# 1.net
KiCad netlist of a schematic drawn in Altium Designer
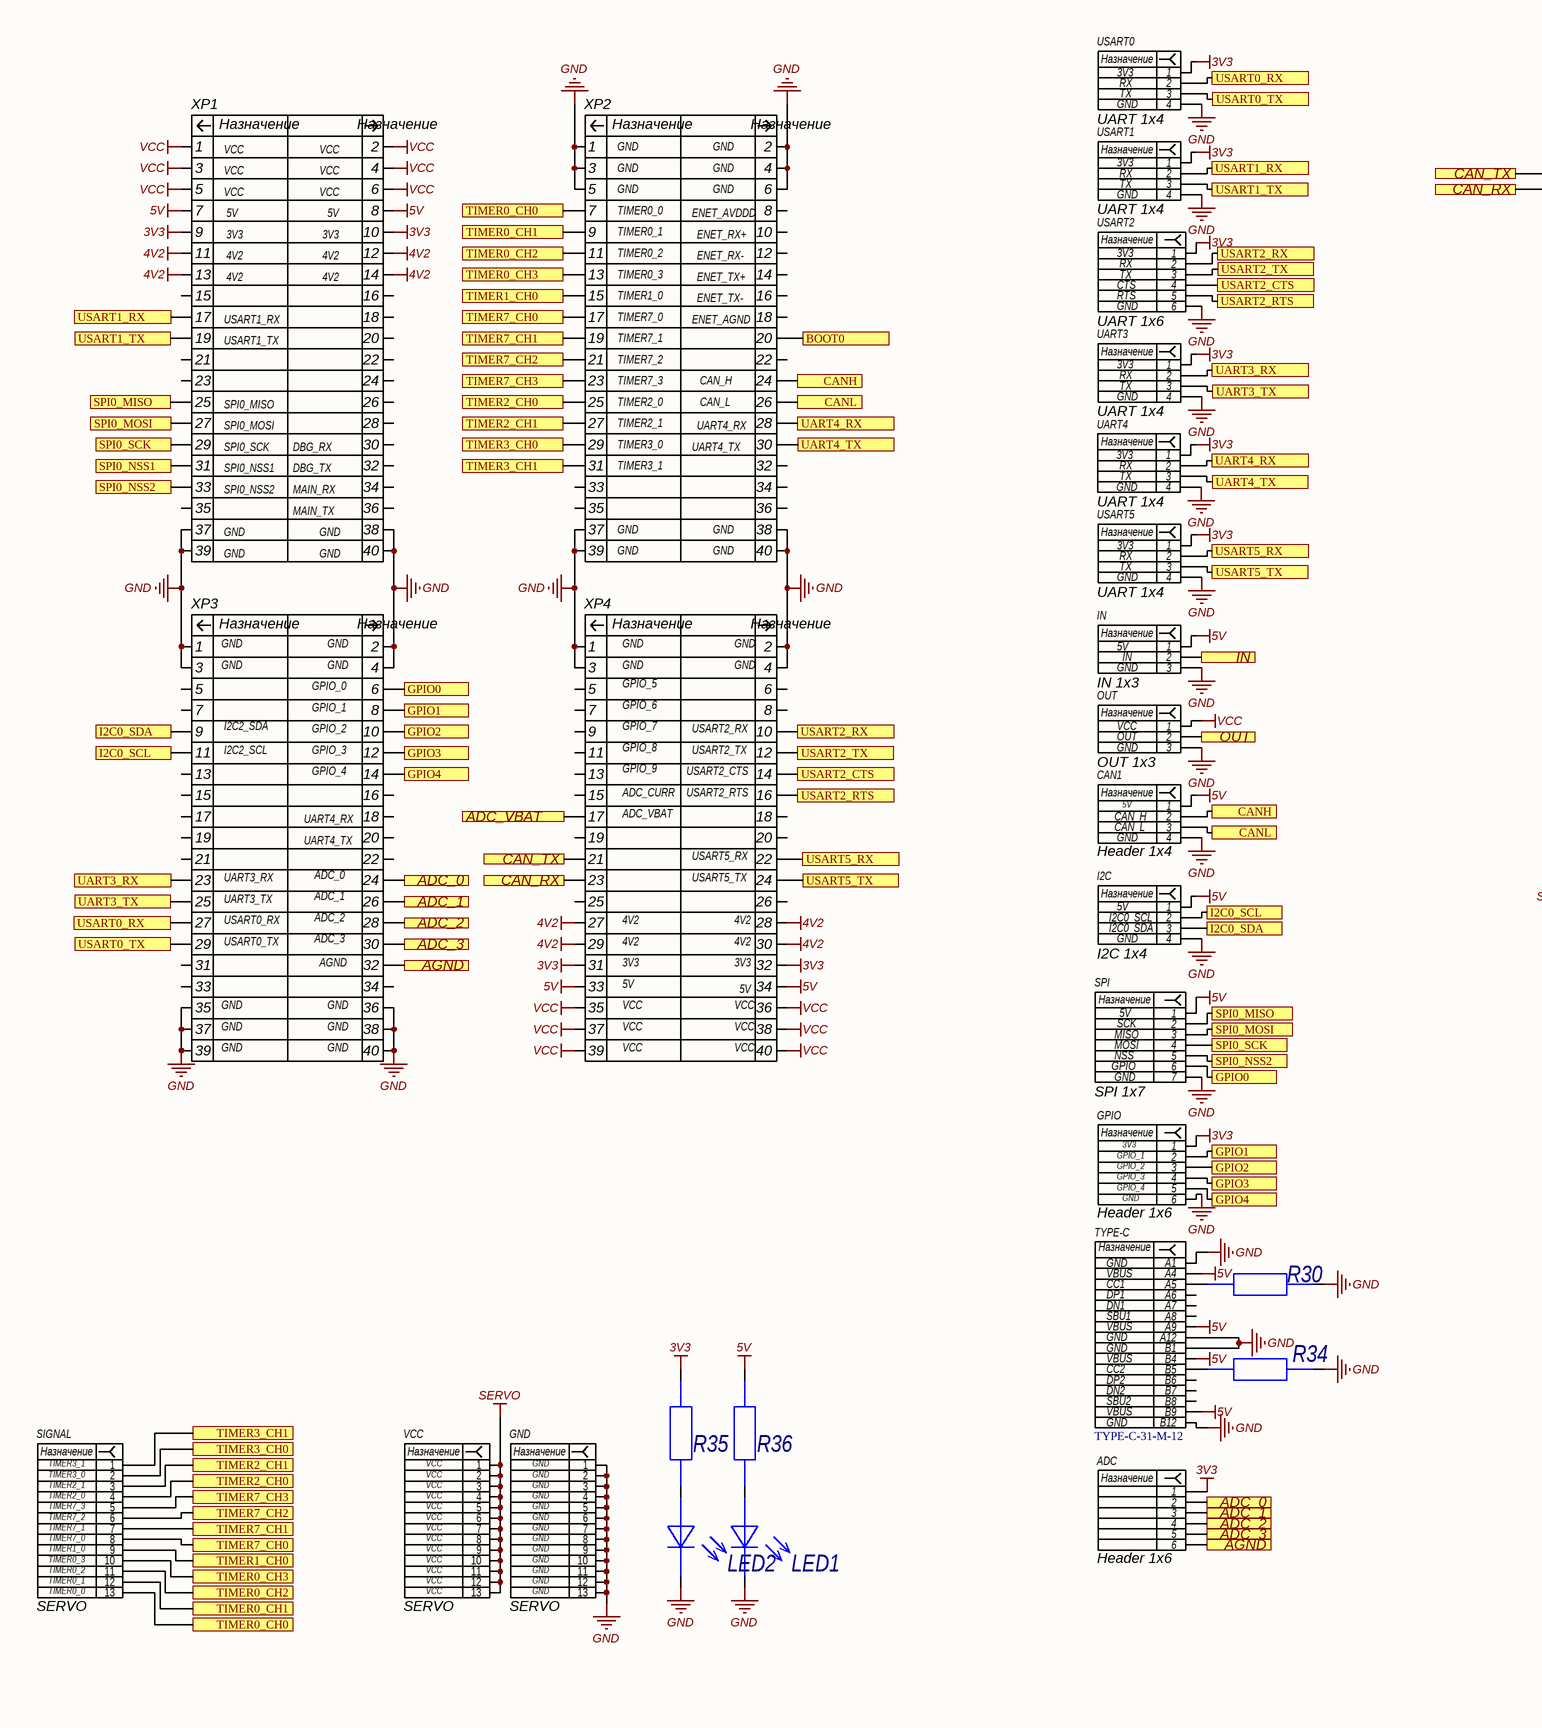
[diagram p0: нижняя плата версия 1.SchDoc, left]
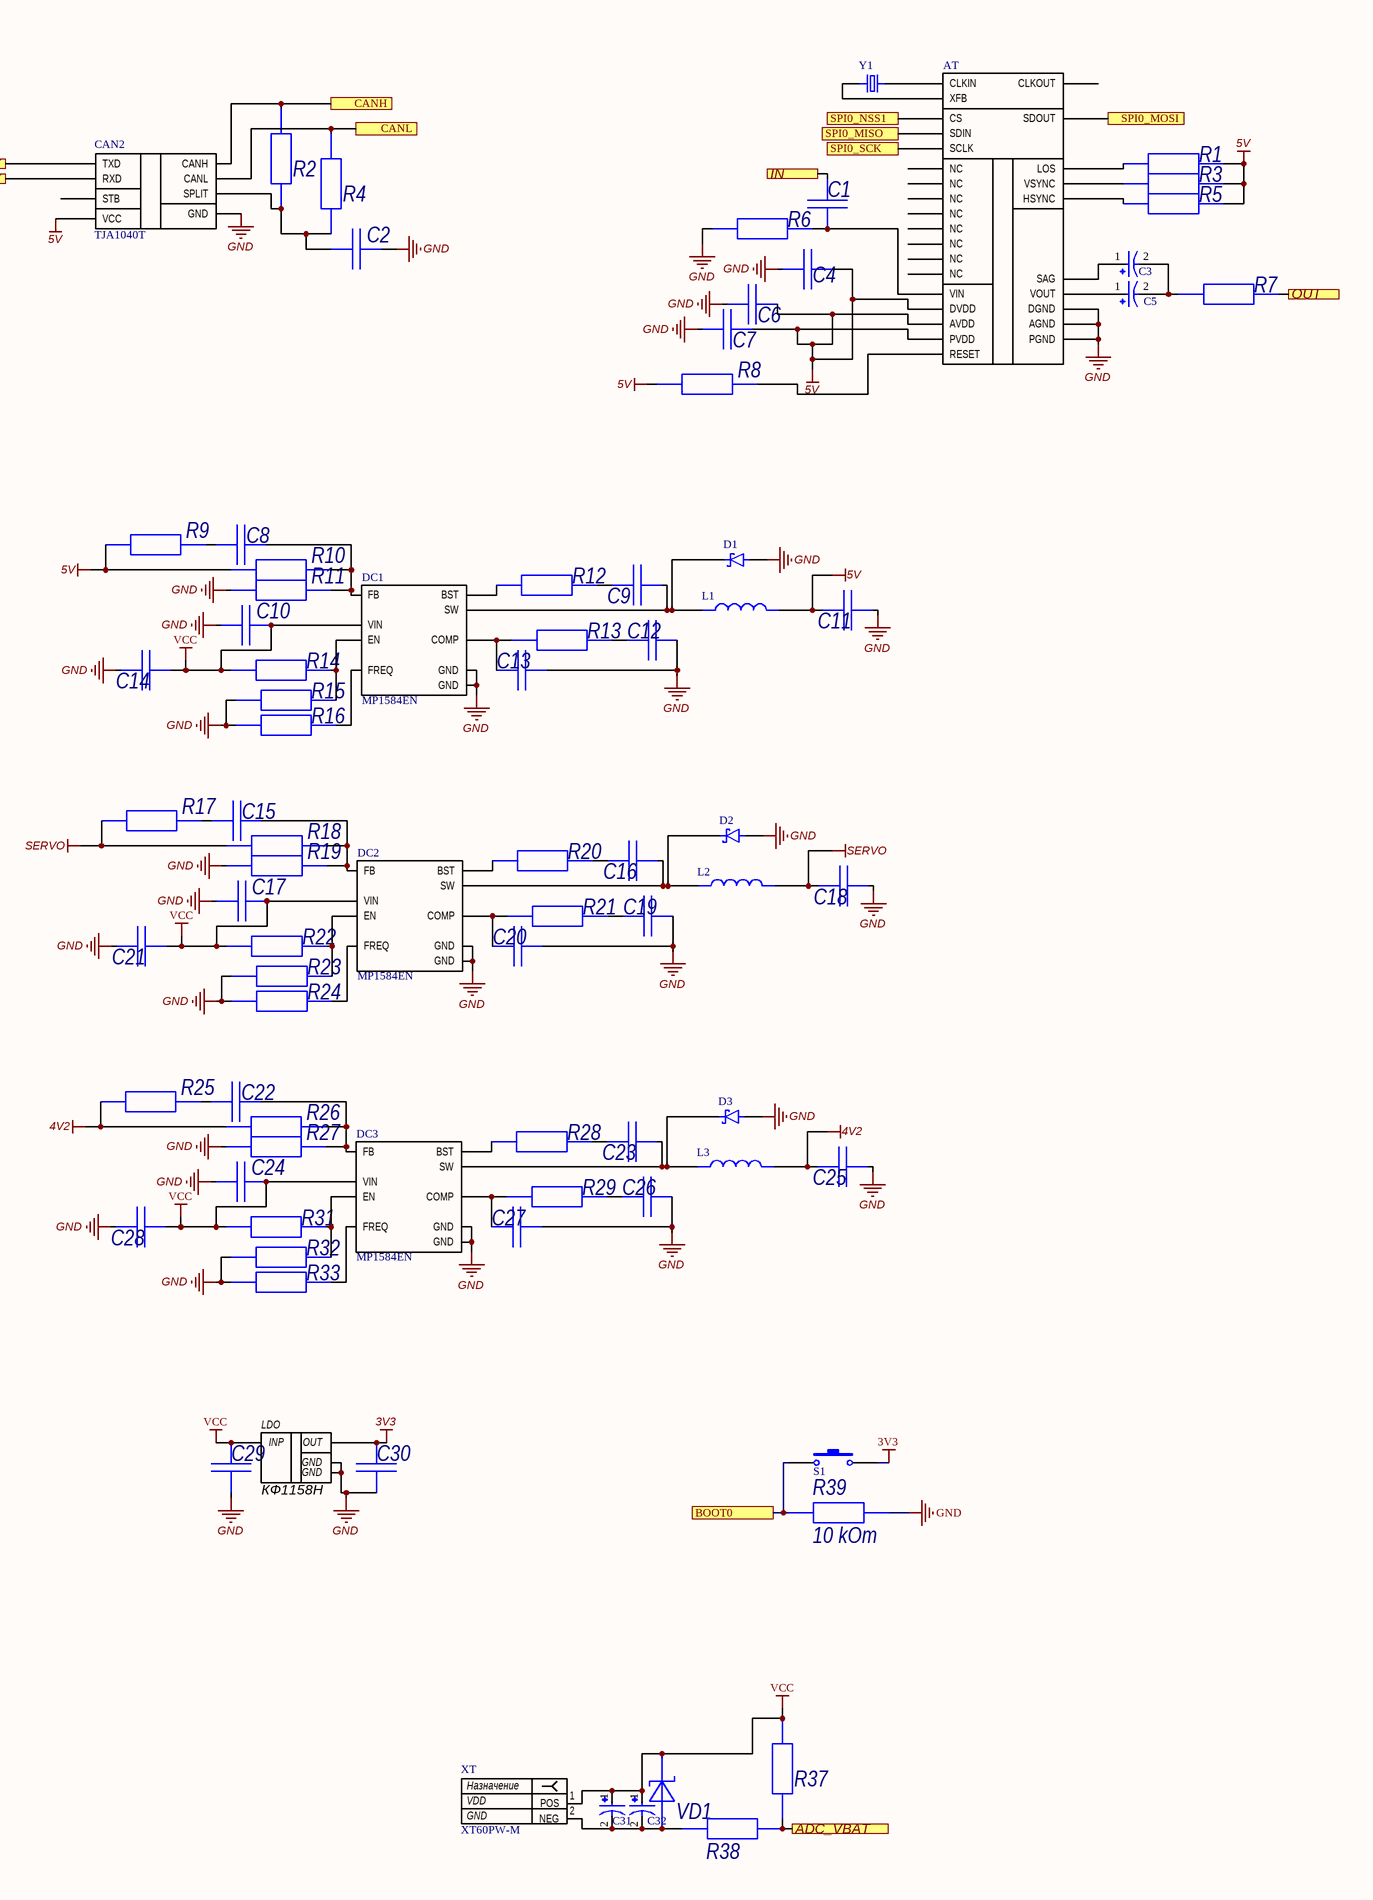
[diagram p1: нижняя плата версия 1.SchDoc, right]

(export (version "E")
  (design (tool "Eeschema 10.0.6"))
  (components
    (comp (ref "ADC")
      (value "Header 1x6")
      (footprint "PicoBlade 6pin")
      (libsource (lib "полётный контроллер") (part "Header 1x6"))
    )
    (comp (ref "AT")
      (value "AT7456")
      (footprint "at7456")
      (description "OSD")
      (libsource (lib "полётный контроллер") (part "AT7456"))
    )
    (comp (ref "C1")
      (value "Capacitor")
      (footprint "C0603")
      (fields (field (name "PUBLISHER") "Andrew Danich"))
      (libsource (lib "Capacitor GOST") (part "Capacitor"))
    )
    (comp (ref "C2")
      (value "4.7 uF")
      (footprint "C0603")
      (fields (field (name "PUBLISHER") "Andrew Danich"))
      (libsource (lib "Capacitor GOST") (part "Capacitor"))
    )
    (comp (ref "C3")
      (value "T493B105K025BC6120")
      (footprint "CAPPM3528X210N")
      (description "Tantalum Surface Mount Capacitors")
      (fields (field (name "MF") "KEMET"))
      (libsource (lib "") (part "T493B105K025BC6120_1"))
    )
    (comp (ref "C4")
      (value "Capacitor")
      (footprint "C0603")
      (fields (field (name "PUBLISHER") "Andrew Danich"))
      (libsource (lib "Capacitor GOST") (part "Capacitor"))
    )
    (comp (ref "C5")
      (value "T493B105K025BC6120")
      (footprint "CAPPM3528X210N")
      (description "Tantalum Surface Mount Capacitors")
      (fields (field (name "MF") "KEMET"))
      (libsource (lib "") (part "T493B105K025BC6120_1"))
    )
    (comp (ref "C6")
      (value "Capacitor")
      (footprint "C0603")
      (fields (field (name "PUBLISHER") "Andrew Danich"))
      (libsource (lib "Capacitor GOST") (part "Capacitor"))
    )
    (comp (ref "C7")
      (value "Capacitor")
      (footprint "C0603")
      (fields (field (name "PUBLISHER") "Andrew Danich"))
      (libsource (lib "Capacitor GOST") (part "Capacitor"))
    )
    (comp (ref "C8")
      (value "22 pF")
      (footprint "C0603")
      (fields (field (name "PUBLISHER") "Andrew Danich"))
      (libsource (lib "Capacitor GOST") (part "Capacitor"))
    )
    (comp (ref "C9")
      (value "0.1 uF")
      (footprint "C0603")
      (fields (field (name "PUBLISHER") "Andrew Danich"))
      (libsource (lib "Capacitor GOST") (part "Capacitor"))
    )
    (comp (ref "C10")
      (value "0.1 uF")
      (footprint "C0603")
      (fields (field (name "PUBLISHER") "Andrew Danich"))
      (libsource (lib "Capacitor GOST") (part "Capacitor"))
    )
    (comp (ref "C11")
      (value "22 uF")
      (footprint "C0603")
      (fields (field (name "PUBLISHER") "Andrew Danich"))
      (libsource (lib "Capacitor GOST") (part "Capacitor"))
    )
    (comp (ref "C12")
      (value "330 pF")
      (footprint "C0603")
      (fields (field (name "PUBLISHER") "Andrew Danich"))
      (libsource (lib "Capacitor GOST") (part "Capacitor"))
    )
    (comp (ref "C13")
      (value "1 pF")
      (footprint "C0603")
      (fields (field (name "PUBLISHER") "Andrew Danich"))
      (libsource (lib "Capacitor GOST") (part "Capacitor"))
    )
    (comp (ref "C14")
      (value "4.7 uF")
      (footprint "C0603")
      (fields (field (name "PUBLISHER") "Andrew Danich"))
      (libsource (lib "Capacitor GOST") (part "Capacitor"))
    )
    (comp (ref "C15")
      (value "22 pF")
      (footprint "C0603")
      (fields (field (name "PUBLISHER") "Andrew Danich"))
      (libsource (lib "Capacitor GOST") (part "Capacitor"))
    )
    (comp (ref "C16")
      (value "0.1 uF")
      (footprint "C0603")
      (fields (field (name "PUBLISHER") "Andrew Danich"))
      (libsource (lib "Capacitor GOST") (part "Capacitor"))
    )
    (comp (ref "C17")
      (value "0.1 uF")
      (footprint "C0603")
      (fields (field (name "PUBLISHER") "Andrew Danich"))
      (libsource (lib "Capacitor GOST") (part "Capacitor"))
    )
    (comp (ref "C18")
      (value "22 uF")
      (footprint "C0603")
      (fields (field (name "PUBLISHER") "Andrew Danich"))
      (libsource (lib "Capacitor GOST") (part "Capacitor"))
    )
    (comp (ref "C19")
      (value "330 pF")
      (footprint "C0603")
      (fields (field (name "PUBLISHER") "Andrew Danich"))
      (libsource (lib "Capacitor GOST") (part "Capacitor"))
    )
    (comp (ref "C20")
      (value "1 pF")
      (footprint "C0603")
      (fields (field (name "PUBLISHER") "Andrew Danich"))
      (libsource (lib "Capacitor GOST") (part "Capacitor"))
    )
    (comp (ref "C21")
      (value "4.7 uF")
      (footprint "C0603")
      (fields (field (name "PUBLISHER") "Andrew Danich"))
      (libsource (lib "Capacitor GOST") (part "Capacitor"))
    )
    (comp (ref "C22")
      (value "22 pF")
      (footprint "C0603")
      (fields (field (name "PUBLISHER") "Andrew Danich"))
      (libsource (lib "Capacitor GOST") (part "Capacitor"))
    )
    (comp (ref "C23")
      (value "0.1 uF")
      (footprint "C0603")
      (fields (field (name "PUBLISHER") "Andrew Danich"))
      (libsource (lib "Capacitor GOST") (part "Capacitor"))
    )
    (comp (ref "C24")
      (value "0.1 uF")
      (footprint "C0603")
      (fields (field (name "PUBLISHER") "Andrew Danich"))
      (libsource (lib "Capacitor GOST") (part "Capacitor"))
    )
    (comp (ref "C25")
      (value "33 uF")
      (footprint "C0603")
      (fields (field (name "PUBLISHER") "Andrew Danich"))
      (libsource (lib "Capacitor GOST") (part "Capacitor"))
    )
    (comp (ref "C26")
      (value "330 pF")
      (footprint "C0603")
      (fields (field (name "PUBLISHER") "Andrew Danich"))
      (libsource (lib "Capacitor GOST") (part "Capacitor"))
    )
    (comp (ref "C27")
      (value "2 pF")
      (footprint "C0603")
      (fields (field (name "PUBLISHER") "Andrew Danich"))
      (libsource (lib "Capacitor GOST") (part "Capacitor"))
    )
    (comp (ref "C28")
      (value "4.7 uF")
      (footprint "C0603")
      (fields (field (name "PUBLISHER") "Andrew Danich"))
      (libsource (lib "Capacitor GOST") (part "Capacitor"))
    )
    (comp (ref "C29")
      (value "0.1 uF")
      (footprint "C0603")
      (fields (field (name "PUBLISHER") "Andrew Danich"))
      (libsource (lib "Capacitor GOST") (part "Capacitor"))
    )
    (comp (ref "C30")
      (value "10 uF")
      (footprint "C0603")
      (fields (field (name "PUBLISHER") "Andrew Danich"))
      (libsource (lib "Capacitor GOST") (part "Capacitor"))
    )
    (comp (ref "C31")
      (value "T493B105K025BC6120")
      (footprint "CAPPM3528X210N")
      (description "Tantalum Surface Mount Capacitors")
      (fields (field (name "MF") "KEMET"))
      (libsource (lib "T493B105K025BC6120") (part "T493B105K025BC6120"))
    )
    (comp (ref "C32")
      (value "T493B105K025BC6120")
      (footprint "CAPPM3528X210N")
      (description "Tantalum Surface Mount Capacitors")
      (fields (field (name "MF") "KEMET"))
      (libsource (lib "T493B105K025BC6120") (part "T493B105K025BC6120"))
    )
    (comp (ref "CAN1")
      (value "Header 1x4")
      (footprint "PicoBlade 4pin")
      (libsource (lib "полётный контроллер") (part "Header 1x4"))
    )
    (comp (ref "CAN2")
      (value "TJA1040T")
      (footprint "SO-8_S")
      (libsource (lib "полётный контроллер") (part "TJA1040T"))
    )
    (comp (ref "D1")
      (value "B340A-13-F")
      (footprint "DIOM5226X240N")
      (description "Diode, Rectifier, 3a, 40v, Do-214ac, Full Reel")
      (libsource (lib "B340A-13-F") (part "B340A-13-F"))
    )
    (comp (ref "D2")
      (value "B340A-13-F")
      (footprint "DIOM5226X240N")
      (description "Diode, Rectifier, 3a, 40v, Do-214ac, Full Reel")
      (libsource (lib "B340A-13-F") (part "B340A-13-F"))
    )
    (comp (ref "D3")
      (value "B340A-13-F")
      (footprint "DIOM5226X240N")
      (description "Diode, Rectifier, 3a, 40v, Do-214ac, Full Reel")
      (libsource (lib "B340A-13-F") (part "B340A-13-F"))
    )
    (comp (ref "DC1")
      (value "MP1584EN")
      (footprint "SOIC127P600X170-9N")
      (libsource (lib "полётный контроллер") (part "MP1584EN"))
    )
    (comp (ref "DC2")
      (value "MP1584EN")
      (footprint "SOIC127P600X170-9N")
      (libsource (lib "полётный контроллер") (part "MP1584EN"))
    )
    (comp (ref "DC3")
      (value "MP1584EN")
      (footprint "SOIC127P600X170-9N")
      (libsource (lib "полётный контроллер") (part "MP1584EN"))
    )
    (comp (ref "GND")
      (value "SERVO")
      (footprint "SERV")
      (libsource (lib "полётный контроллер") (part "SERVO"))
    )
    (comp (ref "GPIO")
      (value "Header 1x6")
      (footprint "PicoBlade 6pin")
      (libsource (lib "полётный контроллер") (part "Header 1x6"))
    )
    (comp (ref "I2C")
      (value "I2C 1x4")
      (footprint "PicoBlade 4pin")
      (libsource (lib "полётный контроллер") (part "I2C 1x4"))
    )
    (comp (ref "IN")
      (value "IN 1x3")
      (footprint "PicoBlade 3pin")
      (libsource (lib "полётный контроллер") (part "IN 1x3"))
    )
    (comp (ref "L1")
      (value "12.3 uH")
      (footprint "IND_VLS6045EX-150M")
      (description "15 ÂµH Shielded Drum Core, Wirewound Inductor 2.5 A 75mOhm Nonstandard")
      (fields (field (name "MF") "TDK") (field (name "MP") "VLS6045EX-150M"))
      (libsource (lib "VLS6045EX-150M") (part "VLS6045EX-150M"))
    )
    (comp (ref "L2")
      (value "12.3 uH")
      (footprint "IND_VLS6045EX-150M")
      (description "15 ÂµH Shielded Drum Core, Wirewound Inductor 2.5 A 75mOhm Nonstandard")
      (fields (field (name "MF") "TDK") (field (name "MP") "VLS6045EX-150M"))
      (libsource (lib "VLS6045EX-150M") (part "VLS6045EX-150M"))
    )
    (comp (ref "L3")
      (value "12.3 uH")
      (footprint "IND_VLS6045EX-150M")
      (description "15 ÂµH Shielded Drum Core, Wirewound Inductor 2.5 A 75mOhm Nonstandard")
      (fields (field (name "MF") "TDK") (field (name "MP") "VLS6045EX-150M"))
      (libsource (lib "VLS6045EX-150M") (part "VLS6045EX-150M"))
    )
    (comp (ref "LDO")
      (value "КФ1158Н")
      (footprint "ТО-263")
      (libsource (lib "полётный контроллер") (part "КФ1158Н"))
    )
    (comp (ref "LED1")
      (value "Text")
      (footprint "LD0805")
      (fields (field (name "PUBLISHER") "Andrew Danich"))
      (libsource (lib "Led GOST") (part "Led-1"))
    )
    (comp (ref "LED2")
      (value "Text")
      (footprint "LD0805")
      (fields (field (name "PUBLISHER") "Andrew Danich"))
      (libsource (lib "Led GOST") (part "Led-1"))
    )
    (comp (ref "OUT")
      (value "OUT 1x3")
      (footprint "PicoBlade 3pin")
      (libsource (lib "полётный контроллер") (part "OUT 1x3"))
    )
    (comp (ref "R1")
      (value "1 kOm")
      (footprint "R0603")
      (fields (field (name "PUBLISHER") "Andrew Danich"))
      (libsource (lib "Resistor GOST") (part "Resistor"))
    )
    (comp (ref "R2")
      (value "~")
      (footprint "R0603")
      (fields (field (name "PUBLISHER") "Andrew Danich"))
      (libsource (lib "Resistor GOST") (part "Resistor"))
    )
    (comp (ref "R3")
      (value "1 kOm")
      (footprint "R0603")
      (fields (field (name "PUBLISHER") "Andrew Danich"))
      (libsource (lib "Resistor GOST") (part "Resistor"))
    )
    (comp (ref "R4")
      (value "~")
      (footprint "R0603")
      (fields (field (name "PUBLISHER") "Andrew Danich"))
      (libsource (lib "Resistor GOST") (part "Resistor"))
    )
    (comp (ref "R5")
      (value "1 kOm")
      (footprint "R0603")
      (fields (field (name "PUBLISHER") "Andrew Danich"))
      (libsource (lib "Resistor GOST") (part "Resistor"))
    )
    (comp (ref "R6")
      (value "10 kOm")
      (footprint "R0603")
      (fields (field (name "PUBLISHER") "Andrew Danich"))
      (libsource (lib "Resistor GOST") (part "Resistor"))
    )
    (comp (ref "R7")
      (value "10 kOm")
      (footprint "R0603")
      (fields (field (name "PUBLISHER") "Andrew Danich"))
      (libsource (lib "Resistor GOST") (part "Resistor"))
    )
    (comp (ref "R8")
      (value "10 kOm")
      (footprint "R0603")
      (fields (field (name "PUBLISHER") "Andrew Danich"))
      (libsource (lib "Resistor GOST") (part "Resistor"))
    )
    (comp (ref "R9")
      (value "0")
      (footprint "R0603")
      (fields (field (name "PUBLISHER") "Andrew Danich"))
      (libsource (lib "Resistor GOST") (part "Resistor"))
    )
    (comp (ref "R10")
      (value "124 kOm")
      (footprint "R0603")
      (fields (field (name "PUBLISHER") "Andrew Danich"))
      (libsource (lib "Resistor GOST") (part "Resistor"))
    )
    (comp (ref "R11")
      (value "23.7 kOm")
      (footprint "R0603")
      (fields (field (name "PUBLISHER") "Andrew Danich"))
      (libsource (lib "Resistor GOST") (part "Resistor"))
    )
    (comp (ref "R12")
      (value "0")
      (footprint "R0603")
      (fields (field (name "PUBLISHER") "Andrew Danich"))
      (libsource (lib "Resistor GOST") (part "Resistor"))
    )
    (comp (ref "R13")
      (value "76.8 kOm")
      (footprint "R0603")
      (fields (field (name "PUBLISHER") "Andrew Danich"))
      (libsource (lib "Resistor GOST") (part "Resistor"))
    )
    (comp (ref "R14")
      (value "100 kOm")
      (footprint "R0603")
      (fields (field (name "PUBLISHER") "Andrew Danich"))
      (libsource (lib "Resistor GOST") (part "Resistor"))
    )
    (comp (ref "R15")
      (value "18.7 kOm")
      (footprint "R0603")
      (fields (field (name "PUBLISHER") "Andrew Danich"))
      (libsource (lib "Resistor GOST") (part "Resistor"))
    )
    (comp (ref "R16")
      (value "193.38 kOm")
      (footprint "R0603")
      (fields (field (name "PUBLISHER") "Andrew Danich"))
      (libsource (lib "Resistor GOST") (part "Resistor"))
    )
    (comp (ref "R17")
      (value "0")
      (footprint "R0603")
      (fields (field (name "PUBLISHER") "Andrew Danich"))
      (libsource (lib "Resistor GOST") (part "Resistor"))
    )
    (comp (ref "R18")
      (value "124 kOm")
      (footprint "R0603")
      (fields (field (name "PUBLISHER") "Andrew Danich"))
      (libsource (lib "Resistor GOST") (part "Resistor"))
    )
    (comp (ref "R19")
      (value "23.7 kOm")
      (footprint "R0603")
      (fields (field (name "PUBLISHER") "Andrew Danich"))
      (libsource (lib "Resistor GOST") (part "Resistor"))
    )
    (comp (ref "R20")
      (value "0")
      (footprint "R0603")
      (fields (field (name "PUBLISHER") "Andrew Danich"))
      (libsource (lib "Resistor GOST") (part "Resistor"))
    )
    (comp (ref "R21")
      (value "76.8 kOm")
      (footprint "R0603")
      (fields (field (name "PUBLISHER") "Andrew Danich"))
      (libsource (lib "Resistor GOST") (part "Resistor"))
    )
    (comp (ref "R22")
      (value "100 kOm")
      (footprint "R0603")
      (fields (field (name "PUBLISHER") "Andrew Danich"))
      (libsource (lib "Resistor GOST") (part "Resistor"))
    )
    (comp (ref "R23")
      (value "18.7 kOm")
      (footprint "R0603")
      (fields (field (name "PUBLISHER") "Andrew Danich"))
      (libsource (lib "Resistor GOST") (part "Resistor"))
    )
    (comp (ref "R24")
      (value "193.38 kOm")
      (footprint "R0603")
      (fields (field (name "PUBLISHER") "Andrew Danich"))
      (libsource (lib "Resistor GOST") (part "Resistor"))
    )
    (comp (ref "R25")
      (value "0")
      (footprint "R0603")
      (fields (field (name "PUBLISHER") "Andrew Danich"))
      (libsource (lib "Resistor GOST") (part "Resistor"))
    )
    (comp (ref "R26")
      (value "124 kOm")
      (footprint "R0603")
      (fields (field (name "PUBLISHER") "Andrew Danich"))
      (libsource (lib "Resistor GOST") (part "Resistor"))
    )
    (comp (ref "R27")
      (value "29 kOm")
      (footprint "R0603")
      (fields (field (name "PUBLISHER") "Andrew Danich"))
      (libsource (lib "Resistor GOST") (part "Resistor"))
    )
    (comp (ref "R28")
      (value "0")
      (footprint "R0603")
      (fields (field (name "PUBLISHER") "Andrew Danich"))
      (libsource (lib "Resistor GOST") (part "Resistor"))
    )
    (comp (ref "R29")
      (value "100 kOm")
      (footprint "R0603")
      (fields (field (name "PUBLISHER") "Andrew Danich"))
      (libsource (lib "Resistor GOST") (part "Resistor"))
    )
    (comp (ref "R30")
      (value "10 kOm")
      (footprint "R0603")
      (fields (field (name "PUBLISHER") "Andrew Danich"))
      (libsource (lib "Resistor GOST") (part "Resistor"))
    )
    (comp (ref "R31")
      (value "100 kOm")
      (footprint "R0603")
      (fields (field (name "PUBLISHER") "Andrew Danich"))
      (libsource (lib "Resistor GOST") (part "Resistor"))
    )
    (comp (ref "R32")
      (value "18.7 kOm")
      (footprint "R0603")
      (fields (field (name "PUBLISHER") "Andrew Danich"))
      (libsource (lib "Resistor GOST") (part "Resistor"))
    )
    (comp (ref "R33")
      (value "193.38 kOm")
      (footprint "R0603")
      (fields (field (name "PUBLISHER") "Andrew Danich"))
      (libsource (lib "Resistor GOST") (part "Resistor"))
    )
    (comp (ref "R34")
      (value "10 kOm")
      (footprint "R0603")
      (fields (field (name "PUBLISHER") "Andrew Danich"))
      (libsource (lib "Resistor GOST") (part "Resistor"))
    )
    (comp (ref "R35")
      (value "10 kOm")
      (footprint "R0603")
      (fields (field (name "PUBLISHER") "Andrew Danich"))
      (libsource (lib "Resistor GOST") (part "Resistor"))
    )
    (comp (ref "R36")
      (value "10 kOm")
      (footprint "R0603")
      (fields (field (name "PUBLISHER") "Andrew Danich"))
      (libsource (lib "Resistor GOST") (part "Resistor"))
    )
    (comp (ref "R37")
      (value "~")
      (footprint "R0603")
      (fields (field (name "PUBLISHER") "Andrew Danich"))
      (libsource (lib "Resistor GOST") (part "Resistor"))
    )
    (comp (ref "R38")
      (value "~")
      (footprint "R0603")
      (fields (field (name "PUBLISHER") "Andrew Danich"))
      (libsource (lib "Resistor GOST") (part "Resistor"))
    )
    (comp (ref "R39")
      (value "10 kOm")
      (footprint "R0603")
      (fields (field (name "PUBLISHER") "Andrew Danich"))
      (libsource (lib "Resistor GOST") (part "Resistor"))
    )
    (comp (ref "S1")
      (value "SW-PB")
      (footprint "SWIT")
      (description "Switch")
      (fields (field (name "PUBLISHER") "Altium Limited"))
      (libsource (lib "Miscellaneous Devices") (part "SW-PB"))
    )
    (comp (ref "SIGNAL")
      (value "SERVO")
      (footprint "SERV")
      (libsource (lib "полётный контроллер") (part "SERVO"))
    )
    (comp (ref "SPI")
      (value "SPI 1x7")
      (footprint "PicoBlade 7pin")
      (libsource (lib "полётный контроллер") (part "SPI 1x7"))
    )
    (comp (ref "TYPE-C")
      (value "TYPE-C-31-M-12")
      (footprint "HRO_TYPE-C-31-M-12")
      (libsource (lib "полётный контроллер") (part "TYPE-C-31-M-12"))
    )
    (comp (ref "UART3")
      (value "UART 1x4")
      (footprint "PicoBlade 4pin")
      (libsource (lib "полётный контроллер") (part "UART 1x4"))
    )
    (comp (ref "UART4")
      (value "UART 1x4")
      (footprint "PicoBlade 4pin")
      (libsource (lib "полётный контроллер") (part "UART 1x4"))
    )
    (comp (ref "USART0")
      (value "UART 1x4")
      (footprint "PicoBlade 4pin")
      (libsource (lib "полётный контроллер") (part "UART 1x4"))
    )
    (comp (ref "USART1")
      (value "UART 1x4")
      (footprint "PicoBlade 4pin")
      (libsource (lib "полётный контроллер") (part "UART 1x4"))
    )
    (comp (ref "USART2")
      (value "UART 1x6")
      (footprint "PicoBlade 6pin")
      (libsource (lib "полётный контроллер") (part "UART 1x6"))
    )
    (comp (ref "USART5")
      (value "UART 1x4")
      (footprint "PicoBlade 4pin")
      (libsource (lib "полётный контроллер") (part "UART 1x4"))
    )
    (comp (ref "VCC")
      (value "SERVO")
      (footprint "SERV")
      (libsource (lib "полётный контроллер") (part "SERVO"))
    )
    (comp (ref "VD1")
      (value "Schottky")
      (footprint "DO-214AA")
      (fields (field (name "PUBLISHER") "Andrew Danich"))
      (libsource (lib "Diode GOST") (part "Schottky"))
    )
    (comp (ref "XP1")
      (value "PLLD-1.27-40S")
      (footprint "Headr 2x20 male")
      (libsource (lib "Разьемы_PLLD_PBD") (part "PLLD-1.27-40S"))
    )
    (comp (ref "XP2")
      (value "PLLD-1.27-40S")
      (footprint "Headr 2x20 male")
      (libsource (lib "Разьемы_PLLD_PBD") (part "PLLD-1.27-40S"))
    )
    (comp (ref "XP3")
      (value "PLLD-1.27-40S")
      (footprint "Headr 2x20 male")
      (libsource (lib "Разьемы_PLLD_PBD") (part "PLLD-1.27-40S"))
    )
    (comp (ref "XP4")
      (value "PLLD-1.27-40S")
      (footprint "Headr 2x20 male")
      (libsource (lib "Разьемы_PLLD_PBD") (part "PLLD-1.27-40S"))
    )
    (comp (ref "XT")
      (value "XT60PW-M")
      (footprint "AMASS_XT60PW-M")
      (libsource (lib "полётный контроллер") (part "XT60PW-M"))
    )
    (comp (ref "Y1")
      (value "ABM7-8.000MHZ-8-R80-D2Y-T")
      (footprint "XTAL_ABM7-8.000MHZ-8-R80-D2Y-T")
      (description "Crystal 22.1184MHz Ã‚Â±20ppm (Tol) Ã‚Â±30ppm (Stability) 18pF FUND 50Ohm 2-Pin Mini-CSMD T/R")
      (libsource (lib "ABM7-8.000MHZ-8-R80-D2Y-T") (part "ABM7-8.000MHZ-8-R80-D2Y-T"))
    )
  )
  (nets
    (net (code "1") (name "/ADC_0") (class "Default")
      (node (ref "ADC") (pin "2") (pinfunction "2_2") (pintype "passive"))
      (node (ref "XP3") (pin "24") (pinfunction "24_24") (pintype "passive"))
    )
    (net (code "2") (name "/ADC_1") (class "Default")
      (node (ref "ADC") (pin "3") (pinfunction "3_3") (pintype "passive"))
      (node (ref "XP3") (pin "26") (pinfunction "26_26") (pintype "passive"))
    )
    (net (code "3") (name "/ADC_2") (class "Default")
      (node (ref "ADC") (pin "4") (pinfunction "4_4") (pintype "passive"))
      (node (ref "XP3") (pin "28") (pinfunction "28_28") (pintype "passive"))
    )
    (net (code "4") (name "/ADC_3") (class "Default")
      (node (ref "ADC") (pin "5") (pinfunction "5_5") (pintype "passive"))
      (node (ref "XP3") (pin "30") (pinfunction "30_30") (pintype "passive"))
    )
    (net (code "5") (name "/ADC_VBAT") (class "Default")
      (node (ref "R37") (pin "2") (pinfunction "2_2") (pintype "passive"))
      (node (ref "R38") (pin "2") (pinfunction "2_2") (pintype "passive"))
      (node (ref "XP4") (pin "17") (pinfunction "17_17") (pintype "passive"))
    )
    (net (code "6") (name "/AGND") (class "Default")
      (node (ref "ADC") (pin "6") (pinfunction "6_6") (pintype "passive"))
      (node (ref "XP3") (pin "32") (pinfunction "32_32") (pintype "passive"))
    )
    (net (code "7") (name "/BOOT0") (class "Default")
      (node (ref "R39") (pin "2") (pinfunction "2_2") (pintype "passive"))
      (node (ref "S1") (pin "1") (pinfunction "1_1") (pintype "passive"))
      (node (ref "XP2") (pin "20") (pinfunction "20_20") (pintype "passive"))
    )
    (net (code "8") (name "/CANH") (class "Default")
      (node (ref "CAN1") (pin "2") (pinfunction "2_2") (pintype "passive"))
      (node (ref "CAN2") (pin "7") (pinfunction "CANH_7") (pintype "passive"))
      (node (ref "R2") (pin "1") (pinfunction "1_1") (pintype "passive"))
      (node (ref "XP2") (pin "24") (pinfunction "24_24") (pintype "passive"))
    )
    (net (code "9") (name "/CANL") (class "Default")
      (node (ref "CAN1") (pin "3") (pinfunction "3_3") (pintype "passive"))
      (node (ref "CAN2") (pin "6") (pinfunction "CANL_6") (pintype "passive"))
      (node (ref "R4") (pin "1") (pinfunction "1_1") (pintype "passive"))
      (node (ref "XP2") (pin "26") (pinfunction "26_26") (pintype "passive"))
    )
    (net (code "10") (name "/CAN_RX") (class "Default")
      (node (ref "CAN2") (pin "4") (pinfunction "RXD_4") (pintype "passive"))
      (node (ref "XP4") (pin "23") (pinfunction "23_23") (pintype "passive"))
    )
    (net (code "11") (name "/CAN_TX") (class "Default")
      (node (ref "CAN2") (pin "1") (pinfunction "TXD_1") (pintype "passive"))
      (node (ref "XP4") (pin "21") (pinfunction "21_21") (pintype "passive"))
    )
    (net (code "12") (name "/GPIO0") (class "Default")
      (node (ref "SPI") (pin "6") (pinfunction "6_6") (pintype "passive"))
      (node (ref "XP3") (pin "6") (pinfunction "6_6") (pintype "passive"))
    )
    (net (code "13") (name "/GPIO1") (class "Default")
      (node (ref "GPIO") (pin "2") (pinfunction "2_2") (pintype "passive"))
      (node (ref "XP3") (pin "8") (pinfunction "8_8") (pintype "passive"))
    )
    (net (code "14") (name "/GPIO2") (class "Default")
      (node (ref "GPIO") (pin "3") (pinfunction "3_3") (pintype "passive"))
      (node (ref "XP3") (pin "10") (pinfunction "10_10") (pintype "passive"))
    )
    (net (code "15") (name "/GPIO3") (class "Default")
      (node (ref "GPIO") (pin "4") (pinfunction "4_4") (pintype "passive"))
      (node (ref "XP3") (pin "12") (pinfunction "12_12") (pintype "passive"))
    )
    (net (code "16") (name "/GPIO4") (class "Default")
      (node (ref "GPIO") (pin "5") (pinfunction "5_5") (pintype "passive"))
      (node (ref "XP3") (pin "14") (pinfunction "14_14") (pintype "passive"))
    )
    (net (code "17") (name "/I2C0_SCL") (class "Default")
      (node (ref "I2C") (pin "2") (pinfunction "2_2") (pintype "passive"))
      (node (ref "XP3") (pin "11") (pinfunction "11_11") (pintype "passive"))
    )
    (net (code "18") (name "/I2C0_SDA") (class "Default")
      (node (ref "I2C") (pin "3") (pinfunction "3_3") (pintype "passive"))
      (node (ref "XP3") (pin "9") (pinfunction "9_9") (pintype "passive"))
    )
    (net (code "19") (name "/IN") (class "Default")
      (node (ref "C1") (pin "2") (pinfunction "2_2") (pintype "passive"))
      (node (ref "IN") (pin "2") (pinfunction "2_2") (pintype "passive"))
    )
    (net (code "20") (name "/OUT") (class "Default")
      (node (ref "OUT") (pin "2") (pinfunction "2_2") (pintype "passive"))
      (node (ref "R7") (pin "2") (pinfunction "2_2") (pintype "passive"))
    )
    (net (code "21") (name "/SPI0_MISO") (class "Default")
      (node (ref "AT") (pin "9") (pinfunction "SDIN_9") (pintype "passive"))
      (node (ref "SPI") (pin "2") (pinfunction "2_2") (pintype "passive"))
      (node (ref "XP1") (pin "25") (pinfunction "25_25") (pintype "passive"))
    )
    (net (code "22") (name "/SPI0_MOSI") (class "Default")
      (node (ref "AT") (pin "11") (pinfunction "SDOUT_11") (pintype "passive"))
      (node (ref "SPI") (pin "3") (pinfunction "3_3") (pintype "passive"))
      (node (ref "XP1") (pin "27") (pinfunction "27_27") (pintype "passive"))
    )
    (net (code "23") (name "/SPI0_NSS1") (class "Default")
      (node (ref "AT") (pin "8") (pinfunction "CS_8") (pintype "passive"))
      (node (ref "XP1") (pin "31") (pinfunction "31_31") (pintype "passive"))
    )
    (net (code "24") (name "/SPI0_NSS2") (class "Default")
      (node (ref "SPI") (pin "5") (pinfunction "5_5") (pintype "passive"))
      (node (ref "XP1") (pin "33") (pinfunction "33_33") (pintype "passive"))
    )
    (net (code "25") (name "/SPI0_SCK") (class "Default")
      (node (ref "AT") (pin "10") (pinfunction "SCLK_10") (pintype "passive"))
      (node (ref "SPI") (pin "4") (pinfunction "4_4") (pintype "passive"))
      (node (ref "XP1") (pin "29") (pinfunction "29_29") (pintype "passive"))
    )
    (net (code "26") (name "/TIMER0_CH0") (class "Default")
      (node (ref "SIGNAL") (pin "13") (pinfunction "13_13") (pintype "passive"))
      (node (ref "XP2") (pin "7") (pinfunction "7_7") (pintype "passive"))
    )
    (net (code "27") (name "/TIMER0_CH1") (class "Default")
      (node (ref "SIGNAL") (pin "12") (pinfunction "12_12") (pintype "passive"))
      (node (ref "XP2") (pin "9") (pinfunction "9_9") (pintype "passive"))
    )
    (net (code "28") (name "/TIMER0_CH2") (class "Default")
      (node (ref "SIGNAL") (pin "11") (pinfunction "11_11") (pintype "passive"))
      (node (ref "XP2") (pin "11") (pinfunction "11_11") (pintype "passive"))
    )
    (net (code "29") (name "/TIMER0_CH3") (class "Default")
      (node (ref "SIGNAL") (pin "10") (pinfunction "10_10") (pintype "passive"))
      (node (ref "XP2") (pin "13") (pinfunction "13_13") (pintype "passive"))
    )
    (net (code "30") (name "/TIMER1_CH0") (class "Default")
      (node (ref "SIGNAL") (pin "9") (pinfunction "9_9") (pintype "passive"))
      (node (ref "XP2") (pin "15") (pinfunction "15_15") (pintype "passive"))
    )
    (net (code "31") (name "/TIMER2_CH0") (class "Default")
      (node (ref "SIGNAL") (pin "4") (pinfunction "4_4") (pintype "passive"))
      (node (ref "XP2") (pin "25") (pinfunction "25_25") (pintype "passive"))
    )
    (net (code "32") (name "/TIMER2_CH1") (class "Default")
      (node (ref "SIGNAL") (pin "3") (pinfunction "3_3") (pintype "passive"))
      (node (ref "XP2") (pin "27") (pinfunction "27_27") (pintype "passive"))
    )
    (net (code "33") (name "/TIMER3_CH0") (class "Default")
      (node (ref "SIGNAL") (pin "2") (pinfunction "2_2") (pintype "passive"))
      (node (ref "XP2") (pin "29") (pinfunction "29_29") (pintype "passive"))
    )
    (net (code "34") (name "/TIMER3_CH1") (class "Default")
      (node (ref "SIGNAL") (pin "1") (pinfunction "1_1") (pintype "passive"))
      (node (ref "XP2") (pin "31") (pinfunction "31_31") (pintype "passive"))
    )
    (net (code "35") (name "/TIMER7_CH0") (class "Default")
      (node (ref "SIGNAL") (pin "8") (pinfunction "8_8") (pintype "passive"))
      (node (ref "XP2") (pin "17") (pinfunction "17_17") (pintype "passive"))
    )
    (net (code "36") (name "/TIMER7_CH1") (class "Default")
      (node (ref "SIGNAL") (pin "7") (pinfunction "7_7") (pintype "passive"))
      (node (ref "XP2") (pin "19") (pinfunction "19_19") (pintype "passive"))
    )
    (net (code "37") (name "/TIMER7_CH2") (class "Default")
      (node (ref "SIGNAL") (pin "6") (pinfunction "6_6") (pintype "passive"))
      (node (ref "XP2") (pin "21") (pinfunction "21_21") (pintype "passive"))
    )
    (net (code "38") (name "/TIMER7_CH3") (class "Default")
      (node (ref "SIGNAL") (pin "5") (pinfunction "5_5") (pintype "passive"))
      (node (ref "XP2") (pin "23") (pinfunction "23_23") (pintype "passive"))
    )
    (net (code "39") (name "/UART3_RX") (class "Default")
      (node (ref "UART3") (pin "2") (pinfunction "2_2") (pintype "passive"))
      (node (ref "XP3") (pin "23") (pinfunction "23_23") (pintype "passive"))
    )
    (net (code "40") (name "/UART3_TX") (class "Default")
      (node (ref "UART3") (pin "3") (pinfunction "3_3") (pintype "passive"))
      (node (ref "XP3") (pin "25") (pinfunction "25_25") (pintype "passive"))
    )
    (net (code "41") (name "/UART4_RX") (class "Default")
      (node (ref "UART4") (pin "2") (pinfunction "2_2") (pintype "passive"))
      (node (ref "XP2") (pin "28") (pinfunction "28_28") (pintype "passive"))
    )
    (net (code "42") (name "/UART4_TX") (class "Default")
      (node (ref "UART4") (pin "3") (pinfunction "3_3") (pintype "passive"))
      (node (ref "XP2") (pin "30") (pinfunction "30_30") (pintype "passive"))
    )
    (net (code "43") (name "/USART0_RX") (class "Default")
      (node (ref "USART0") (pin "2") (pinfunction "2_2") (pintype "passive"))
      (node (ref "XP3") (pin "27") (pinfunction "27_27") (pintype "passive"))
    )
    (net (code "44") (name "/USART0_TX") (class "Default")
      (node (ref "USART0") (pin "3") (pinfunction "3_3") (pintype "passive"))
      (node (ref "XP3") (pin "29") (pinfunction "29_29") (pintype "passive"))
    )
    (net (code "45") (name "/USART1_RX") (class "Default")
      (node (ref "USART1") (pin "2") (pinfunction "2_2") (pintype "passive"))
      (node (ref "XP1") (pin "17") (pinfunction "17_17") (pintype "passive"))
    )
    (net (code "46") (name "/USART1_TX") (class "Default")
      (node (ref "USART1") (pin "3") (pinfunction "3_3") (pintype "passive"))
      (node (ref "XP1") (pin "19") (pinfunction "19_19") (pintype "passive"))
    )
    (net (code "47") (name "/USART2_CTS") (class "Default")
      (node (ref "USART2") (pin "4") (pinfunction "4_4") (pintype "passive"))
      (node (ref "XP4") (pin "14") (pinfunction "14_14") (pintype "passive"))
    )
    (net (code "48") (name "/USART2_RTS") (class "Default")
      (node (ref "USART2") (pin "5") (pinfunction "5_5") (pintype "passive"))
      (node (ref "XP4") (pin "16") (pinfunction "16_16") (pintype "passive"))
    )
    (net (code "49") (name "/USART2_RX") (class "Default")
      (node (ref "USART2") (pin "2") (pinfunction "2_2") (pintype "passive"))
      (node (ref "XP4") (pin "10") (pinfunction "10_10") (pintype "passive"))
    )
    (net (code "50") (name "/USART2_TX") (class "Default")
      (node (ref "USART2") (pin "3") (pinfunction "3_3") (pintype "passive"))
      (node (ref "XP4") (pin "12") (pinfunction "12_12") (pintype "passive"))
    )
    (net (code "51") (name "/USART5_RX") (class "Default")
      (node (ref "USART5") (pin "2") (pinfunction "2_2") (pintype "passive"))
      (node (ref "XP4") (pin "22") (pinfunction "22_22") (pintype "passive"))
    )
    (net (code "52") (name "/USART5_TX") (class "Default")
      (node (ref "USART5") (pin "3") (pinfunction "3_3") (pintype "passive"))
      (node (ref "XP4") (pin "24") (pinfunction "24_24") (pintype "passive"))
    )
    (net (code "53") (name "3V3") (class "Default")
      (node (ref "ADC") (pin "1") (pinfunction "1_1") (pintype "passive"))
      (node (ref "C30") (pin "2") (pinfunction "2_2") (pintype "passive"))
      (node (ref "GPIO") (pin "1") (pinfunction "1_1") (pintype "passive"))
      (node (ref "LDO") (pin "3") (pinfunction "OUT_3") (pintype "passive"))
      (node (ref "R35") (pin "2") (pinfunction "2_2") (pintype "passive"))
      (node (ref "S1") (pin "2") (pinfunction "2_2") (pintype "passive"))
      (node (ref "UART3") (pin "1") (pinfunction "1_1") (pintype "passive"))
      (node (ref "UART4") (pin "1") (pinfunction "1_1") (pintype "passive"))
      (node (ref "USART0") (pin "1") (pinfunction "1_1") (pintype "passive"))
      (node (ref "USART1") (pin "1") (pinfunction "1_1") (pintype "passive"))
      (node (ref "USART2") (pin "1") (pinfunction "1_1") (pintype "passive"))
      (node (ref "USART5") (pin "1") (pinfunction "1_1") (pintype "passive"))
      (node (ref "XP1") (pin "10") (pinfunction "10_10") (pintype "passive"))
      (node (ref "XP1") (pin "9") (pinfunction "9_9") (pintype "passive"))
      (node (ref "XP4") (pin "31") (pinfunction "31_31") (pintype "passive"))
      (node (ref "XP4") (pin "32") (pinfunction "32_32") (pintype "passive"))
    )
    (net (code "54") (name "4V2") (class "Default")
      (node (ref "C25") (pin "1") (pinfunction "1_1") (pintype "passive"))
      (node (ref "L3") (pin "2") (pinfunction "2_2") (pintype "passive"))
      (node (ref "R25") (pin "2") (pinfunction "2_2") (pintype "passive"))
      (node (ref "R26") (pin "2") (pinfunction "2_2") (pintype "passive"))
      (node (ref "XP1") (pin "11") (pinfunction "11_11") (pintype "passive"))
      (node (ref "XP1") (pin "12") (pinfunction "12_12") (pintype "passive"))
      (node (ref "XP1") (pin "13") (pinfunction "13_13") (pintype "passive"))
      (node (ref "XP1") (pin "14") (pinfunction "14_14") (pintype "passive"))
      (node (ref "XP4") (pin "27") (pinfunction "27_27") (pintype "passive"))
      (node (ref "XP4") (pin "28") (pinfunction "28_28") (pintype "passive"))
      (node (ref "XP4") (pin "29") (pinfunction "29_29") (pintype "passive"))
      (node (ref "XP4") (pin "30") (pinfunction "30_30") (pintype "passive"))
    )
    (net (code "55") (name "5V") (class "Default")
      (node (ref "AT") (pin "21") (pinfunction "AVDD_21") (pintype "passive"))
      (node (ref "AT") (pin "24") (pinfunction "PVDD_24") (pintype "passive"))
      (node (ref "AT") (pin "3") (pinfunction "DVDD_3") (pintype "passive"))
      (node (ref "C11") (pin "1") (pinfunction "1_1") (pintype "passive"))
      (node (ref "C4") (pin "1") (pinfunction "1_1") (pintype "passive"))
      (node (ref "C6") (pin "1") (pinfunction "1_1") (pintype "passive"))
      (node (ref "C7") (pin "1") (pinfunction "1_1") (pintype "passive"))
      (node (ref "CAN1") (pin "1") (pinfunction "1_1") (pintype "passive"))
      (node (ref "CAN2") (pin "3") (pinfunction "VCC_3") (pintype "power_in"))
      (node (ref "I2C") (pin "1") (pinfunction "1_1") (pintype "passive"))
      (node (ref "IN") (pin "1") (pinfunction "1_1") (pintype "passive"))
      (node (ref "L1") (pin "2") (pinfunction "2_2") (pintype "passive"))
      (node (ref "R1") (pin "2") (pinfunction "2_2") (pintype "passive"))
      (node (ref "R10") (pin "2") (pinfunction "2_2") (pintype "passive"))
      (node (ref "R3") (pin "2") (pinfunction "2_2") (pintype "passive"))
      (node (ref "R36") (pin "2") (pinfunction "2_2") (pintype "passive"))
      (node (ref "R5") (pin "2") (pinfunction "2_2") (pintype "passive"))
      (node (ref "R8") (pin "2") (pinfunction "2_2") (pintype "passive"))
      (node (ref "R9") (pin "2") (pinfunction "2_2") (pintype "passive"))
      (node (ref "SPI") (pin "1") (pinfunction "1_1") (pintype "passive"))
      (node (ref "TYPE-C") (pin "10") (pinfunction "B4_10") (pintype "passive"))
      (node (ref "TYPE-C") (pin "15") (pinfunction "B9_15") (pintype "passive"))
      (node (ref "TYPE-C") (pin "2") (pinfunction "A4_2") (pintype "passive"))
      (node (ref "TYPE-C") (pin "7") (pinfunction "A9_7") (pintype "passive"))
      (node (ref "XP1") (pin "7") (pinfunction "7_7") (pintype "passive"))
      (node (ref "XP1") (pin "8") (pinfunction "8_8") (pintype "passive"))
      (node (ref "XP4") (pin "33") (pinfunction "33_33") (pintype "passive"))
      (node (ref "XP4") (pin "34") (pinfunction "34_34") (pintype "passive"))
    )
    (net (code "56") (name "GND") (class "Default")
      (node (ref "AT") (pin "20") (pinfunction "AGND_20") (pintype "passive"))
      (node (ref "AT") (pin "23") (pinfunction "PGND_23") (pintype "passive"))
      (node (ref "AT") (pin "4") (pinfunction "DGND_4") (pintype "passive"))
      (node (ref "C10") (pin "1") (pinfunction "1_1") (pintype "passive"))
      (node (ref "C11") (pin "2") (pinfunction "2_2") (pintype "passive"))
      (node (ref "C12") (pin "2") (pinfunction "2_2") (pintype "passive"))
      (node (ref "C13") (pin "2") (pinfunction "2_2") (pintype "passive"))
      (node (ref "C14") (pin "1") (pinfunction "1_1") (pintype "passive"))
      (node (ref "C17") (pin "1") (pinfunction "1_1") (pintype "passive"))
      (node (ref "C18") (pin "2") (pinfunction "2_2") (pintype "passive"))
      (node (ref "C19") (pin "2") (pinfunction "2_2") (pintype "passive"))
      (node (ref "C2") (pin "1") (pinfunction "1_1") (pintype "passive"))
      (node (ref "C20") (pin "2") (pinfunction "2_2") (pintype "passive"))
      (node (ref "C21") (pin "1") (pinfunction "1_1") (pintype "passive"))
      (node (ref "C24") (pin "1") (pinfunction "1_1") (pintype "passive"))
      (node (ref "C25") (pin "2") (pinfunction "2_2") (pintype "passive"))
      (node (ref "C26") (pin "2") (pinfunction "2_2") (pintype "passive"))
      (node (ref "C27") (pin "2") (pinfunction "2_2") (pintype "passive"))
      (node (ref "C28") (pin "1") (pinfunction "1_1") (pintype "passive"))
      (node (ref "C29") (pin "1") (pinfunction "1_1") (pintype "passive"))
      (node (ref "C30") (pin "1") (pinfunction "1_1") (pintype "passive"))
      (node (ref "C4") (pin "2") (pinfunction "2_2") (pintype "passive"))
      (node (ref "C6") (pin "2") (pinfunction "2_2") (pintype "passive"))
      (node (ref "C7") (pin "2") (pinfunction "2_2") (pintype "passive"))
      (node (ref "CAN1") (pin "4") (pinfunction "4_4") (pintype "passive"))
      (node (ref "CAN2") (pin "2") (pinfunction "GND_2") (pintype "passive"))
      (node (ref "D1") (pin "A") (pinfunction "A_A") (pintype "passive"))
      (node (ref "D2") (pin "A") (pinfunction "A_A") (pintype "passive"))
      (node (ref "D3") (pin "A") (pinfunction "A_A") (pintype "passive"))
      (node (ref "DC1") (pin "5") (pinfunction "GND_5") (pintype "passive"))
      (node (ref "DC1") (pin "9") (pinfunction "GND_9") (pintype "passive"))
      (node (ref "DC2") (pin "5") (pinfunction "GND_5") (pintype "passive"))
      (node (ref "DC2") (pin "9") (pinfunction "GND_9") (pintype "passive"))
      (node (ref "DC3") (pin "5") (pinfunction "GND_5") (pintype "passive"))
      (node (ref "DC3") (pin "9") (pinfunction "GND_9") (pintype "passive"))
      (node (ref "GND") (pin "1") (pinfunction "1_1") (pintype "passive"))
      (node (ref "GND") (pin "10") (pinfunction "10_10") (pintype "passive"))
      (node (ref "GND") (pin "11") (pinfunction "11_11") (pintype "passive"))
      (node (ref "GND") (pin "12") (pinfunction "12_12") (pintype "passive"))
      (node (ref "GND") (pin "13") (pinfunction "13_13") (pintype "passive"))
      (node (ref "GND") (pin "2") (pinfunction "2_2") (pintype "passive"))
      (node (ref "GND") (pin "3") (pinfunction "3_3") (pintype "passive"))
      (node (ref "GND") (pin "4") (pinfunction "4_4") (pintype "passive"))
      (node (ref "GND") (pin "5") (pinfunction "5_5") (pintype "passive"))
      (node (ref "GND") (pin "6") (pinfunction "6_6") (pintype "passive"))
      (node (ref "GND") (pin "7") (pinfunction "7_7") (pintype "passive"))
      (node (ref "GND") (pin "8") (pinfunction "8_8") (pintype "passive"))
      (node (ref "GND") (pin "9") (pinfunction "9_9") (pintype "passive"))
      (node (ref "GPIO") (pin "6") (pinfunction "6_6") (pintype "passive"))
      (node (ref "I2C") (pin "4") (pinfunction "4_4") (pintype "passive"))
      (node (ref "IN") (pin "3") (pinfunction "3_3") (pintype "passive"))
      (node (ref "LDO") (pin "2") (pinfunction "GND_2") (pintype "passive"))
      (node (ref "LDO") (pin "4") (pinfunction "GND_4") (pintype "passive"))
      (node (ref "LED1") (pin "2") (pinfunction "К_2") (pintype "passive"))
      (node (ref "LED2") (pin "2") (pinfunction "К_2") (pintype "passive"))
      (node (ref "OUT") (pin "3") (pinfunction "3_3") (pintype "passive"))
      (node (ref "R11") (pin "2") (pinfunction "2_2") (pintype "passive"))
      (node (ref "R15") (pin "2") (pinfunction "2_2") (pintype "passive"))
      (node (ref "R16") (pin "2") (pinfunction "2_2") (pintype "passive"))
      (node (ref "R19") (pin "2") (pinfunction "2_2") (pintype "passive"))
      (node (ref "R23") (pin "2") (pinfunction "2_2") (pintype "passive"))
      (node (ref "R24") (pin "2") (pinfunction "2_2") (pintype "passive"))
      (node (ref "R27") (pin "2") (pinfunction "2_2") (pintype "passive"))
      (node (ref "R30") (pin "2") (pinfunction "2_2") (pintype "passive"))
      (node (ref "R32") (pin "2") (pinfunction "2_2") (pintype "passive"))
      (node (ref "R33") (pin "2") (pinfunction "2_2") (pintype "passive"))
      (node (ref "R34") (pin "2") (pinfunction "2_2") (pintype "passive"))
      (node (ref "R39") (pin "1") (pinfunction "1_1") (pintype "passive"))
      (node (ref "R6") (pin "1") (pinfunction "1_1") (pintype "passive"))
      (node (ref "SPI") (pin "7") (pinfunction "7_7") (pintype "passive"))
      (node (ref "TYPE-C") (pin "1") (pinfunction "A1_1") (pintype "passive"))
      (node (ref "TYPE-C") (pin "16") (pinfunction "B12_16") (pintype "passive"))
      (node (ref "TYPE-C") (pin "8") (pinfunction "A12_8") (pintype "passive"))
      (node (ref "TYPE-C") (pin "9") (pinfunction "B1_9") (pintype "passive"))
      (node (ref "UART3") (pin "4") (pinfunction "4_4") (pintype "passive"))
      (node (ref "UART4") (pin "4") (pinfunction "4_4") (pintype "passive"))
      (node (ref "USART0") (pin "4") (pinfunction "4_4") (pintype "passive"))
      (node (ref "USART1") (pin "4") (pinfunction "4_4") (pintype "passive"))
      (node (ref "USART2") (pin "6") (pinfunction "6_6") (pintype "passive"))
      (node (ref "USART5") (pin "4") (pinfunction "4_4") (pintype "passive"))
      (node (ref "XP1") (pin "37") (pinfunction "37_37") (pintype "passive"))
      (node (ref "XP1") (pin "38") (pinfunction "38_38") (pintype "passive"))
      (node (ref "XP1") (pin "39") (pinfunction "39_39") (pintype "passive"))
      (node (ref "XP1") (pin "40") (pinfunction "40_40") (pintype "passive"))
      (node (ref "XP2") (pin "1") (pinfunction "1_1") (pintype "passive"))
      (node (ref "XP2") (pin "2") (pinfunction "2_2") (pintype "passive"))
      (node (ref "XP2") (pin "3") (pinfunction "3_3") (pintype "passive"))
      (node (ref "XP2") (pin "37") (pinfunction "37_37") (pintype "passive"))
      (node (ref "XP2") (pin "38") (pinfunction "38_38") (pintype "passive"))
      (node (ref "XP2") (pin "39") (pinfunction "39_39") (pintype "passive"))
      (node (ref "XP2") (pin "4") (pinfunction "4_4") (pintype "passive"))
      (node (ref "XP2") (pin "40") (pinfunction "40_40") (pintype "passive"))
      (node (ref "XP2") (pin "5") (pinfunction "5_5") (pintype "passive"))
      (node (ref "XP2") (pin "6") (pinfunction "6_6") (pintype "passive"))
      (node (ref "XP3") (pin "1") (pinfunction "1_1") (pintype "passive"))
      (node (ref "XP3") (pin "2") (pinfunction "2_2") (pintype "passive"))
      (node (ref "XP3") (pin "3") (pinfunction "3_3") (pintype "passive"))
      (node (ref "XP3") (pin "35") (pinfunction "35_35") (pintype "passive"))
      (node (ref "XP3") (pin "36") (pinfunction "36_36") (pintype "passive"))
      (node (ref "XP3") (pin "37") (pinfunction "37_37") (pintype "passive"))
      (node (ref "XP3") (pin "38") (pinfunction "38_38") (pintype "passive"))
      (node (ref "XP3") (pin "39") (pinfunction "39_39") (pintype "passive"))
      (node (ref "XP3") (pin "4") (pinfunction "4_4") (pintype "passive"))
      (node (ref "XP3") (pin "40") (pinfunction "40_40") (pintype "passive"))
      (node (ref "XP4") (pin "1") (pinfunction "1_1") (pintype "passive"))
      (node (ref "XP4") (pin "2") (pinfunction "2_2") (pintype "passive"))
      (node (ref "XP4") (pin "3") (pinfunction "3_3") (pintype "passive"))
      (node (ref "XP4") (pin "4") (pinfunction "4_4") (pintype "passive"))
    )
    (net (code "57") (name "Net-(AT-CLKIN)") (class "Default")
      (node (ref "AT") (pin "5") (pinfunction "CLKIN_5") (pintype "passive"))
      (node (ref "Y1") (pin "2") (pinfunction "2_2") (pintype "passive"))
    )
    (net (code "58") (name "Net-(AT-HSYNC)") (class "Default")
      (node (ref "AT") (pin "18") (pinfunction "HSYNC_18") (pintype "passive"))
      (node (ref "R5") (pin "1") (pinfunction "1_1") (pintype "passive"))
    )
    (net (code "59") (name "Net-(AT-LOS)") (class "Default")
      (node (ref "AT") (pin "12") (pinfunction "LOS_12") (pintype "passive"))
      (node (ref "R1") (pin "1") (pinfunction "1_1") (pintype "passive"))
    )
    (net (code "60") (name "Net-(AT-RESET)") (class "Default")
      (node (ref "AT") (pin "19") (pinfunction "RESET_19") (pintype "passive"))
      (node (ref "R8") (pin "1") (pinfunction "1_1") (pintype "passive"))
    )
    (net (code "61") (name "Net-(AT-SAG)") (class "Default")
      (node (ref "AT") (pin "25") (pinfunction "SAG_25") (pintype "passive"))
      (node (ref "C3") (pin "1") (pinfunction "1_1") (pintype "passive"))
    )
    (net (code "62") (name "Net-(AT-VIN)") (class "Default")
      (node (ref "AT") (pin "22") (pinfunction "VIN_22") (pintype "passive"))
      (node (ref "C1") (pin "1") (pinfunction "1_1") (pintype "passive"))
      (node (ref "R6") (pin "2") (pinfunction "2_2") (pintype "passive"))
    )
    (net (code "63") (name "Net-(AT-VOUT)") (class "Default")
      (node (ref "AT") (pin "26") (pinfunction "VOUT_26") (pintype "passive"))
      (node (ref "C5") (pin "1") (pinfunction "1_1") (pintype "passive"))
    )
    (net (code "64") (name "Net-(AT-VSYNC)") (class "Default")
      (node (ref "AT") (pin "17") (pinfunction "VSYNC_17") (pintype "passive"))
      (node (ref "R3") (pin "1") (pinfunction "1_1") (pintype "passive"))
    )
    (net (code "65") (name "Net-(AT-XFB)") (class "Default")
      (node (ref "AT") (pin "6") (pinfunction "XFB_6") (pintype "passive"))
      (node (ref "Y1") (pin "1") (pinfunction "1_1") (pintype "passive"))
    )
    (net (code "66") (name "Net-(C3-Pad2)") (class "Default")
      (node (ref "C3") (pin "2") (pinfunction "2_2") (pintype "passive"))
      (node (ref "C5") (pin "2") (pinfunction "2_2") (pintype "passive"))
      (node (ref "R7") (pin "1") (pinfunction "1_1") (pintype "passive"))
    )
    (net (code "67") (name "Net-(C8-Pad1)") (class "Default")
      (node (ref "C8") (pin "1") (pinfunction "1_1") (pintype "passive"))
      (node (ref "R9") (pin "1") (pinfunction "1_1") (pintype "passive"))
    )
    (net (code "68") (name "Net-(C9-Pad1)") (class "Default")
      (node (ref "C9") (pin "1") (pinfunction "1_1") (pintype "passive"))
      (node (ref "R12") (pin "1") (pinfunction "1_1") (pintype "passive"))
    )
    (net (code "69") (name "Net-(C12-Pad1)") (class "Default")
      (node (ref "C12") (pin "1") (pinfunction "1_1") (pintype "passive"))
      (node (ref "R13") (pin "1") (pinfunction "1_1") (pintype "passive"))
    )
    (net (code "70") (name "Net-(C15-Pad1)") (class "Default")
      (node (ref "C15") (pin "1") (pinfunction "1_1") (pintype "passive"))
      (node (ref "R17") (pin "1") (pinfunction "1_1") (pintype "passive"))
    )
    (net (code "71") (name "Net-(C16-Pad1)") (class "Default")
      (node (ref "C16") (pin "1") (pinfunction "1_1") (pintype "passive"))
      (node (ref "R20") (pin "1") (pinfunction "1_1") (pintype "passive"))
    )
    (net (code "72") (name "Net-(C19-Pad1)") (class "Default")
      (node (ref "C19") (pin "1") (pinfunction "1_1") (pintype "passive"))
      (node (ref "R21") (pin "1") (pinfunction "1_1") (pintype "passive"))
    )
    (net (code "73") (name "Net-(C22-Pad1)") (class "Default")
      (node (ref "C22") (pin "1") (pinfunction "1_1") (pintype "passive"))
      (node (ref "R25") (pin "1") (pinfunction "1_1") (pintype "passive"))
    )
    (net (code "74") (name "Net-(C23-Pad1)") (class "Default")
      (node (ref "C23") (pin "1") (pinfunction "1_1") (pintype "passive"))
      (node (ref "R28") (pin "1") (pinfunction "1_1") (pintype "passive"))
    )
    (net (code "75") (name "Net-(C26-Pad1)") (class "Default")
      (node (ref "C26") (pin "1") (pinfunction "1_1") (pintype "passive"))
      (node (ref "R29") (pin "1") (pinfunction "1_1") (pintype "passive"))
    )
    (net (code "76") (name "Net-(CAN2-SPLIT)") (class "Default")
      (node (ref "C2") (pin "2") (pinfunction "2_2") (pintype "passive"))
      (node (ref "CAN2") (pin "5") (pinfunction "SPLIT_5") (pintype "passive"))
      (node (ref "R2") (pin "2") (pinfunction "2_2") (pintype "passive"))
      (node (ref "R4") (pin "2") (pinfunction "2_2") (pintype "passive"))
    )
    (net (code "77") (name "Net-(DC1-BST)") (class "Default")
      (node (ref "DC1") (pin "8") (pinfunction "BST_8") (pintype "passive"))
      (node (ref "R12") (pin "2") (pinfunction "2_2") (pintype "passive"))
    )
    (net (code "78") (name "Net-(DC1-COMP)") (class "Default")
      (node (ref "C13") (pin "1") (pinfunction "1_1") (pintype "passive"))
      (node (ref "DC1") (pin "3") (pinfunction "COMP_3") (pintype "passive"))
      (node (ref "R13") (pin "2") (pinfunction "2_2") (pintype "passive"))
    )
    (net (code "79") (name "Net-(DC1-EN)") (class "Default")
      (node (ref "DC1") (pin "2") (pinfunction "EN_2") (pintype "passive"))
      (node (ref "R14") (pin "1") (pinfunction "1_1") (pintype "passive"))
      (node (ref "R15") (pin "1") (pinfunction "1_1") (pintype "passive"))
    )
    (net (code "80") (name "Net-(DC1-FB)") (class "Default")
      (node (ref "C8") (pin "2") (pinfunction "2_2") (pintype "passive"))
      (node (ref "DC1") (pin "4") (pinfunction "FB_4") (pintype "passive"))
      (node (ref "R10") (pin "1") (pinfunction "1_1") (pintype "passive"))
      (node (ref "R11") (pin "1") (pinfunction "1_1") (pintype "passive"))
    )
    (net (code "81") (name "Net-(DC1-FREQ)") (class "Default")
      (node (ref "DC1") (pin "6") (pinfunction "FREQ_6") (pintype "passive"))
      (node (ref "R16") (pin "1") (pinfunction "1_1") (pintype "passive"))
    )
    (net (code "82") (name "Net-(DC1-SW)") (class "Default")
      (node (ref "C9") (pin "2") (pinfunction "2_2") (pintype "passive"))
      (node (ref "D1") (pin "C") (pinfunction "C_C") (pintype "passive"))
      (node (ref "DC1") (pin "1") (pinfunction "SW_1") (pintype "passive"))
      (node (ref "L1") (pin "1") (pinfunction "1_1") (pintype "passive"))
    )
    (net (code "83") (name "Net-(DC2-BST)") (class "Default")
      (node (ref "DC2") (pin "8") (pinfunction "BST_8") (pintype "passive"))
      (node (ref "R20") (pin "2") (pinfunction "2_2") (pintype "passive"))
    )
    (net (code "84") (name "Net-(DC2-COMP)") (class "Default")
      (node (ref "C20") (pin "1") (pinfunction "1_1") (pintype "passive"))
      (node (ref "DC2") (pin "3") (pinfunction "COMP_3") (pintype "passive"))
      (node (ref "R21") (pin "2") (pinfunction "2_2") (pintype "passive"))
    )
    (net (code "85") (name "Net-(DC2-EN)") (class "Default")
      (node (ref "DC2") (pin "2") (pinfunction "EN_2") (pintype "passive"))
      (node (ref "R22") (pin "1") (pinfunction "1_1") (pintype "passive"))
      (node (ref "R23") (pin "1") (pinfunction "1_1") (pintype "passive"))
    )
    (net (code "86") (name "Net-(DC2-FB)") (class "Default")
      (node (ref "C15") (pin "2") (pinfunction "2_2") (pintype "passive"))
      (node (ref "DC2") (pin "4") (pinfunction "FB_4") (pintype "passive"))
      (node (ref "R18") (pin "1") (pinfunction "1_1") (pintype "passive"))
      (node (ref "R19") (pin "1") (pinfunction "1_1") (pintype "passive"))
    )
    (net (code "87") (name "Net-(DC2-FREQ)") (class "Default")
      (node (ref "DC2") (pin "6") (pinfunction "FREQ_6") (pintype "passive"))
      (node (ref "R24") (pin "1") (pinfunction "1_1") (pintype "passive"))
    )
    (net (code "88") (name "Net-(DC2-SW)") (class "Default")
      (node (ref "C16") (pin "2") (pinfunction "2_2") (pintype "passive"))
      (node (ref "D2") (pin "C") (pinfunction "C_C") (pintype "passive"))
      (node (ref "DC2") (pin "1") (pinfunction "SW_1") (pintype "passive"))
      (node (ref "L2") (pin "1") (pinfunction "1_1") (pintype "passive"))
    )
    (net (code "89") (name "Net-(DC3-BST)") (class "Default")
      (node (ref "DC3") (pin "8") (pinfunction "BST_8") (pintype "passive"))
      (node (ref "R28") (pin "2") (pinfunction "2_2") (pintype "passive"))
    )
    (net (code "90") (name "Net-(DC3-COMP)") (class "Default")
      (node (ref "C27") (pin "1") (pinfunction "1_1") (pintype "passive"))
      (node (ref "DC3") (pin "3") (pinfunction "COMP_3") (pintype "passive"))
      (node (ref "R29") (pin "2") (pinfunction "2_2") (pintype "passive"))
    )
    (net (code "91") (name "Net-(DC3-EN)") (class "Default")
      (node (ref "DC3") (pin "2") (pinfunction "EN_2") (pintype "passive"))
      (node (ref "R31") (pin "1") (pinfunction "1_1") (pintype "passive"))
      (node (ref "R32") (pin "1") (pinfunction "1_1") (pintype "passive"))
    )
    (net (code "92") (name "Net-(DC3-FB)") (class "Default")
      (node (ref "C22") (pin "2") (pinfunction "2_2") (pintype "passive"))
      (node (ref "DC3") (pin "4") (pinfunction "FB_4") (pintype "passive"))
      (node (ref "R26") (pin "1") (pinfunction "1_1") (pintype "passive"))
      (node (ref "R27") (pin "1") (pinfunction "1_1") (pintype "passive"))
    )
    (net (code "93") (name "Net-(DC3-FREQ)") (class "Default")
      (node (ref "DC3") (pin "6") (pinfunction "FREQ_6") (pintype "passive"))
      (node (ref "R33") (pin "1") (pinfunction "1_1") (pintype "passive"))
    )
    (net (code "94") (name "Net-(DC3-SW)") (class "Default")
      (node (ref "C23") (pin "2") (pinfunction "2_2") (pintype "passive"))
      (node (ref "D3") (pin "C") (pinfunction "C_C") (pintype "passive"))
      (node (ref "DC3") (pin "1") (pinfunction "SW_1") (pintype "passive"))
      (node (ref "L3") (pin "1") (pinfunction "1_1") (pintype "passive"))
    )
    (net (code "95") (name "Net-(LED1-А)") (class "Default")
      (node (ref "LED1") (pin "1") (pinfunction "А_1") (pintype "passive"))
      (node (ref "R36") (pin "1") (pinfunction "1_1") (pintype "passive"))
    )
    (net (code "96") (name "Net-(LED2-А)") (class "Default")
      (node (ref "LED2") (pin "1") (pinfunction "А_1") (pintype "passive"))
      (node (ref "R35") (pin "1") (pinfunction "1_1") (pintype "passive"))
    )
    (net (code "97") (name "Net-(TYPE-C-A5)") (class "Default")
      (node (ref "R30") (pin "1") (pinfunction "1_1") (pintype "passive"))
      (node (ref "TYPE-C") (pin "3") (pinfunction "A5_3") (pintype "passive"))
    )
    (net (code "98") (name "Net-(TYPE-C-B5)") (class "Default")
      (node (ref "R34") (pin "1") (pinfunction "1_1") (pintype "passive"))
      (node (ref "TYPE-C") (pin "11") (pinfunction "B5_11") (pintype "passive"))
    )
    (net (code "99") (name "Net-(VD1-А)") (class "Default")
      (node (ref "C31") (pin "2") (pinfunction "2_2") (pintype "passive"))
      (node (ref "C32") (pin "2") (pinfunction "2_2") (pintype "passive"))
      (node (ref "R38") (pin "1") (pinfunction "1_1") (pintype "passive"))
      (node (ref "VD1") (pin "1") (pinfunction "А_1") (pintype "passive"))
      (node (ref "XT") (pin "2") (pinfunction "NEG_2") (pintype "passive"))
    )
    (net (code "100") (name "SERVO") (class "Default")
      (node (ref "C18") (pin "1") (pinfunction "1_1") (pintype "passive"))
      (node (ref "L2") (pin "2") (pinfunction "2_2") (pintype "passive"))
      (node (ref "R17") (pin "2") (pinfunction "2_2") (pintype "passive"))
      (node (ref "R18") (pin "2") (pinfunction "2_2") (pintype "passive"))
      (node (ref "VCC") (pin "1") (pinfunction "1_1") (pintype "passive"))
      (node (ref "VCC") (pin "10") (pinfunction "10_10") (pintype "passive"))
      (node (ref "VCC") (pin "11") (pinfunction "11_11") (pintype "passive"))
      (node (ref "VCC") (pin "12") (pinfunction "12_12") (pintype "passive"))
      (node (ref "VCC") (pin "13") (pinfunction "13_13") (pintype "passive"))
      (node (ref "VCC") (pin "2") (pinfunction "2_2") (pintype "passive"))
      (node (ref "VCC") (pin "3") (pinfunction "3_3") (pintype "passive"))
      (node (ref "VCC") (pin "4") (pinfunction "4_4") (pintype "passive"))
      (node (ref "VCC") (pin "5") (pinfunction "5_5") (pintype "passive"))
      (node (ref "VCC") (pin "6") (pinfunction "6_6") (pintype "passive"))
      (node (ref "VCC") (pin "7") (pinfunction "7_7") (pintype "passive"))
      (node (ref "VCC") (pin "8") (pinfunction "8_8") (pintype "passive"))
      (node (ref "VCC") (pin "9") (pinfunction "9_9") (pintype "passive"))
    )
    (net (code "101") (name "VCC") (class "Default")
      (node (ref "C10") (pin "2") (pinfunction "2_2") (pintype "passive"))
      (node (ref "C14") (pin "2") (pinfunction "2_2") (pintype "passive"))
      (node (ref "C17") (pin "2") (pinfunction "2_2") (pintype "passive"))
      (node (ref "C21") (pin "2") (pinfunction "2_2") (pintype "passive"))
      (node (ref "C24") (pin "2") (pinfunction "2_2") (pintype "passive"))
      (node (ref "C28") (pin "2") (pinfunction "2_2") (pintype "passive"))
      (node (ref "C29") (pin "2") (pinfunction "2_2") (pintype "passive"))
      (node (ref "C31") (pin "1") (pinfunction "1_1") (pintype "passive"))
      (node (ref "C32") (pin "1") (pinfunction "1_1") (pintype "passive"))
      (node (ref "DC1") (pin "7") (pinfunction "VIN_7") (pintype "passive"))
      (node (ref "DC2") (pin "7") (pinfunction "VIN_7") (pintype "passive"))
      (node (ref "DC3") (pin "7") (pinfunction "VIN_7") (pintype "passive"))
      (node (ref "LDO") (pin "1") (pinfunction "INP_1") (pintype "passive"))
      (node (ref "OUT") (pin "1") (pinfunction "1_1") (pintype "passive"))
      (node (ref "R14") (pin "2") (pinfunction "2_2") (pintype "passive"))
      (node (ref "R22") (pin "2") (pinfunction "2_2") (pintype "passive"))
      (node (ref "R31") (pin "2") (pinfunction "2_2") (pintype "passive"))
      (node (ref "R37") (pin "1") (pinfunction "1_1") (pintype "passive"))
      (node (ref "VD1") (pin "2") (pinfunction "К_2") (pintype "passive"))
      (node (ref "XP1") (pin "1") (pinfunction "1_1") (pintype "passive"))
      (node (ref "XP1") (pin "2") (pinfunction "2_2") (pintype "passive"))
      (node (ref "XP1") (pin "3") (pinfunction "3_3") (pintype "passive"))
      (node (ref "XP1") (pin "4") (pinfunction "4_4") (pintype "passive"))
      (node (ref "XP1") (pin "5") (pinfunction "5_5") (pintype "passive"))
      (node (ref "XP1") (pin "6") (pinfunction "6_6") (pintype "passive"))
      (node (ref "XP4") (pin "35") (pinfunction "35_35") (pintype "passive"))
      (node (ref "XP4") (pin "36") (pinfunction "36_36") (pintype "passive"))
      (node (ref "XP4") (pin "37") (pinfunction "37_37") (pintype "passive"))
      (node (ref "XP4") (pin "38") (pinfunction "38_38") (pintype "passive"))
      (node (ref "XP4") (pin "39") (pinfunction "39_39") (pintype "passive"))
      (node (ref "XP4") (pin "40") (pinfunction "40_40") (pintype "passive"))
      (node (ref "XT") (pin "1") (pinfunction "POS_1") (pintype "passive"))
    )
    (net (code "102") (name "unconnected-(AT-CLKOUT-Pad7)") (class "Default")
      (node (ref "AT") (pin "7") (pinfunction "CLKOUT_7") (pintype "passive"))
    )
    (net (code "103") (name "unconnected-(AT-NC-Pad1)") (class "Default")
      (node (ref "AT") (pin "1") (pinfunction "NC_1") (pintype "passive"))
    )
    (net (code "104") (name "unconnected-(AT-NC-Pad2)") (class "Default")
      (node (ref "AT") (pin "2") (pinfunction "NC_2") (pintype "passive"))
    )
    (net (code "105") (name "unconnected-(AT-NC-Pad13)") (class "Default")
      (node (ref "AT") (pin "13") (pinfunction "NC_13") (pintype "passive"))
    )
    (net (code "106") (name "unconnected-(AT-NC-Pad14)") (class "Default")
      (node (ref "AT") (pin "14") (pinfunction "NC_14") (pintype "passive"))
    )
    (net (code "107") (name "unconnected-(AT-NC-Pad15)") (class "Default")
      (node (ref "AT") (pin "15") (pinfunction "NC_15") (pintype "passive"))
    )
    (net (code "108") (name "unconnected-(AT-NC-Pad16)") (class "Default")
      (node (ref "AT") (pin "16") (pinfunction "NC_16") (pintype "passive"))
    )
    (net (code "109") (name "unconnected-(AT-NC-Pad27)") (class "Default")
      (node (ref "AT") (pin "27") (pinfunction "NC_27") (pintype "passive"))
    )
    (net (code "110") (name "unconnected-(AT-NC-Pad28)") (class "Default")
      (node (ref "AT") (pin "28") (pinfunction "NC_28") (pintype "passive"))
    )
    (net (code "111") (name "unconnected-(CAN2-STB-Pad8)") (class "Default")
      (node (ref "CAN2") (pin "8") (pinfunction "STB_8") (pintype "passive"))
    )
    (net (code "112") (name "unconnected-(TYPE-C-A6-Pad4)") (class "Default")
      (node (ref "TYPE-C") (pin "4") (pinfunction "A6_4") (pintype "passive"))
    )
    (net (code "113") (name "unconnected-(TYPE-C-A7-Pad5)") (class "Default")
      (node (ref "TYPE-C") (pin "5") (pinfunction "A7_5") (pintype "passive"))
    )
    (net (code "114") (name "unconnected-(TYPE-C-A8-Pad6)") (class "Default")
      (node (ref "TYPE-C") (pin "6") (pinfunction "A8_6") (pintype "passive"))
    )
    (net (code "115") (name "unconnected-(TYPE-C-B6-Pad12)") (class "Default")
      (node (ref "TYPE-C") (pin "12") (pinfunction "B6_12") (pintype "passive"))
    )
    (net (code "116") (name "unconnected-(TYPE-C-B7-Pad13)") (class "Default")
      (node (ref "TYPE-C") (pin "13") (pinfunction "B7_13") (pintype "passive"))
    )
    (net (code "117") (name "unconnected-(TYPE-C-B8-Pad14)") (class "Default")
      (node (ref "TYPE-C") (pin "14") (pinfunction "B8_14") (pintype "passive"))
    )
    (net (code "118") (name "unconnected-(XP1-Pad15)") (class "Default")
      (node (ref "XP1") (pin "15") (pinfunction "15_15") (pintype "passive"))
    )
    (net (code "119") (name "unconnected-(XP1-Pad16)") (class "Default")
      (node (ref "XP1") (pin "16") (pinfunction "16_16") (pintype "passive"))
    )
    (net (code "120") (name "unconnected-(XP1-Pad18)") (class "Default")
      (node (ref "XP1") (pin "18") (pinfunction "18_18") (pintype "passive"))
    )
    (net (code "121") (name "unconnected-(XP1-Pad20)") (class "Default")
      (node (ref "XP1") (pin "20") (pinfunction "20_20") (pintype "passive"))
    )
    (net (code "122") (name "unconnected-(XP1-Pad21)") (class "Default")
      (node (ref "XP1") (pin "21") (pinfunction "21_21") (pintype "passive"))
    )
    (net (code "123") (name "unconnected-(XP1-Pad22)") (class "Default")
      (node (ref "XP1") (pin "22") (pinfunction "22_22") (pintype "passive"))
    )
    (net (code "124") (name "unconnected-(XP1-Pad23)") (class "Default")
      (node (ref "XP1") (pin "23") (pinfunction "23_23") (pintype "passive"))
    )
    (net (code "125") (name "unconnected-(XP1-Pad24)") (class "Default")
      (node (ref "XP1") (pin "24") (pinfunction "24_24") (pintype "passive"))
    )
    (net (code "126") (name "unconnected-(XP1-Pad26)") (class "Default")
      (node (ref "XP1") (pin "26") (pinfunction "26_26") (pintype "passive"))
    )
    (net (code "127") (name "unconnected-(XP1-Pad28)") (class "Default")
      (node (ref "XP1") (pin "28") (pinfunction "28_28") (pintype "passive"))
    )
    (net (code "128") (name "unconnected-(XP1-Pad30)") (class "Default")
      (node (ref "XP1") (pin "30") (pinfunction "30_30") (pintype "passive"))
    )
    (net (code "129") (name "unconnected-(XP1-Pad32)") (class "Default")
      (node (ref "XP1") (pin "32") (pinfunction "32_32") (pintype "passive"))
    )
    (net (code "130") (name "unconnected-(XP1-Pad34)") (class "Default")
      (node (ref "XP1") (pin "34") (pinfunction "34_34") (pintype "passive"))
    )
    (net (code "131") (name "unconnected-(XP1-Pad35)") (class "Default")
      (node (ref "XP1") (pin "35") (pinfunction "35_35") (pintype "passive"))
    )
    (net (code "132") (name "unconnected-(XP1-Pad36)") (class "Default")
      (node (ref "XP1") (pin "36") (pinfunction "36_36") (pintype "passive"))
    )
    (net (code "133") (name "unconnected-(XP2-Pad8)") (class "Default")
      (node (ref "XP2") (pin "8") (pinfunction "8_8") (pintype "passive"))
    )
    (net (code "134") (name "unconnected-(XP2-Pad10)") (class "Default")
      (node (ref "XP2") (pin "10") (pinfunction "10_10") (pintype "passive"))
    )
    (net (code "135") (name "unconnected-(XP2-Pad12)") (class "Default")
      (node (ref "XP2") (pin "12") (pinfunction "12_12") (pintype "passive"))
    )
    (net (code "136") (name "unconnected-(XP2-Pad14)") (class "Default")
      (node (ref "XP2") (pin "14") (pinfunction "14_14") (pintype "passive"))
    )
    (net (code "137") (name "unconnected-(XP2-Pad16)") (class "Default")
      (node (ref "XP2") (pin "16") (pinfunction "16_16") (pintype "passive"))
    )
    (net (code "138") (name "unconnected-(XP2-Pad18)") (class "Default")
      (node (ref "XP2") (pin "18") (pinfunction "18_18") (pintype "passive"))
    )
    (net (code "139") (name "unconnected-(XP2-Pad22)") (class "Default")
      (node (ref "XP2") (pin "22") (pinfunction "22_22") (pintype "passive"))
    )
    (net (code "140") (name "unconnected-(XP2-Pad32)") (class "Default")
      (node (ref "XP2") (pin "32") (pinfunction "32_32") (pintype "passive"))
    )
    (net (code "141") (name "unconnected-(XP2-Pad33)") (class "Default")
      (node (ref "XP2") (pin "33") (pinfunction "33_33") (pintype "passive"))
    )
    (net (code "142") (name "unconnected-(XP2-Pad34)") (class "Default")
      (node (ref "XP2") (pin "34") (pinfunction "34_34") (pintype "passive"))
    )
    (net (code "143") (name "unconnected-(XP2-Pad35)") (class "Default")
      (node (ref "XP2") (pin "35") (pinfunction "35_35") (pintype "passive"))
    )
    (net (code "144") (name "unconnected-(XP2-Pad36)") (class "Default")
      (node (ref "XP2") (pin "36") (pinfunction "36_36") (pintype "passive"))
    )
    (net (code "145") (name "unconnected-(XP3-Pad5)") (class "Default")
      (node (ref "XP3") (pin "5") (pinfunction "5_5") (pintype "passive"))
    )
    (net (code "146") (name "unconnected-(XP3-Pad7)") (class "Default")
      (node (ref "XP3") (pin "7") (pinfunction "7_7") (pintype "passive"))
    )
    (net (code "147") (name "unconnected-(XP3-Pad13)") (class "Default")
      (node (ref "XP3") (pin "13") (pinfunction "13_13") (pintype "passive"))
    )
    (net (code "148") (name "unconnected-(XP3-Pad15)") (class "Default")
      (node (ref "XP3") (pin "15") (pinfunction "15_15") (pintype "passive"))
    )
    (net (code "149") (name "unconnected-(XP3-Pad16)") (class "Default")
      (node (ref "XP3") (pin "16") (pinfunction "16_16") (pintype "passive"))
    )
    (net (code "150") (name "unconnected-(XP3-Pad17)") (class "Default")
      (node (ref "XP3") (pin "17") (pinfunction "17_17") (pintype "passive"))
    )
    (net (code "151") (name "unconnected-(XP3-Pad18)") (class "Default")
      (node (ref "XP3") (pin "18") (pinfunction "18_18") (pintype "passive"))
    )
    (net (code "152") (name "unconnected-(XP3-Pad19)") (class "Default")
      (node (ref "XP3") (pin "19") (pinfunction "19_19") (pintype "passive"))
    )
    (net (code "153") (name "unconnected-(XP3-Pad20)") (class "Default")
      (node (ref "XP3") (pin "20") (pinfunction "20_20") (pintype "passive"))
    )
    (net (code "154") (name "unconnected-(XP3-Pad21)") (class "Default")
      (node (ref "XP3") (pin "21") (pinfunction "21_21") (pintype "passive"))
    )
    (net (code "155") (name "unconnected-(XP3-Pad22)") (class "Default")
      (node (ref "XP3") (pin "22") (pinfunction "22_22") (pintype "passive"))
    )
    (net (code "156") (name "unconnected-(XP3-Pad31)") (class "Default")
      (node (ref "XP3") (pin "31") (pinfunction "31_31") (pintype "passive"))
    )
    (net (code "157") (name "unconnected-(XP3-Pad33)") (class "Default")
      (node (ref "XP3") (pin "33") (pinfunction "33_33") (pintype "passive"))
    )
    (net (code "158") (name "unconnected-(XP3-Pad34)") (class "Default")
      (node (ref "XP3") (pin "34") (pinfunction "34_34") (pintype "passive"))
    )
    (net (code "159") (name "unconnected-(XP4-Pad5)") (class "Default")
      (node (ref "XP4") (pin "5") (pinfunction "5_5") (pintype "passive"))
    )
    (net (code "160") (name "unconnected-(XP4-Pad6)") (class "Default")
      (node (ref "XP4") (pin "6") (pinfunction "6_6") (pintype "passive"))
    )
    (net (code "161") (name "unconnected-(XP4-Pad7)") (class "Default")
      (node (ref "XP4") (pin "7") (pinfunction "7_7") (pintype "passive"))
    )
    (net (code "162") (name "unconnected-(XP4-Pad8)") (class "Default")
      (node (ref "XP4") (pin "8") (pinfunction "8_8") (pintype "passive"))
    )
    (net (code "163") (name "unconnected-(XP4-Pad9)") (class "Default")
      (node (ref "XP4") (pin "9") (pinfunction "9_9") (pintype "passive"))
    )
    (net (code "164") (name "unconnected-(XP4-Pad11)") (class "Default")
      (node (ref "XP4") (pin "11") (pinfunction "11_11") (pintype "passive"))
    )
    (net (code "165") (name "unconnected-(XP4-Pad13)") (class "Default")
      (node (ref "XP4") (pin "13") (pinfunction "13_13") (pintype "passive"))
    )
    (net (code "166") (name "unconnected-(XP4-Pad15)") (class "Default")
      (node (ref "XP4") (pin "15") (pinfunction "15_15") (pintype "passive"))
    )
    (net (code "167") (name "unconnected-(XP4-Pad18)") (class "Default")
      (node (ref "XP4") (pin "18") (pinfunction "18_18") (pintype "passive"))
    )
    (net (code "168") (name "unconnected-(XP4-Pad19)") (class "Default")
      (node (ref "XP4") (pin "19") (pinfunction "19_19") (pintype "passive"))
    )
    (net (code "169") (name "unconnected-(XP4-Pad20)") (class "Default")
      (node (ref "XP4") (pin "20") (pinfunction "20_20") (pintype "passive"))
    )
    (net (code "170") (name "unconnected-(XP4-Pad25)") (class "Default")
      (node (ref "XP4") (pin "25") (pinfunction "25_25") (pintype "passive"))
    )
    (net (code "171") (name "unconnected-(XP4-Pad26)") (class "Default")
      (node (ref "XP4") (pin "26") (pinfunction "26_26") (pintype "passive"))
    )
  )
)
